# sound.net
KiCad netlist of a schematic drawn in Altium Designer
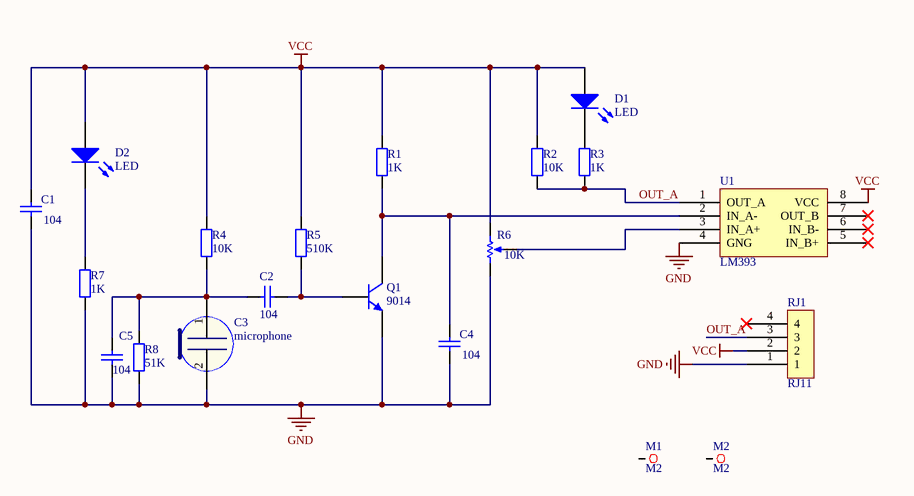
[diagram p0: sound.SchDoc]

(export (version "E")
  (design (tool "Eeschema 10.0.6"))
  (components
    (comp (ref "C1")
      (value "104")
      (footprint "0603_C")
      (description "Capacitor")
      (fields (field (name "Comment") "Cap") (field (name "PUBLISHER") "Altium Limited"))
      (libsource (lib "Miscellaneous Devices") (part "Cap"))
    )
    (comp (ref "C2")
      (value "104")
      (footprint "0603_C")
      (description "Capacitor")
      (fields (field (name "Comment") "Cap") (field (name "PUBLISHER") "Altium Limited"))
      (libsource (lib "Miscellaneous Devices") (part "Cap"))
    )
    (comp (ref "C3")
      (value "microphone")
      (footprint "Microphone")
      (libsource (lib "sound") (part "microphone"))
    )
    (comp (ref "C4")
      (value "104")
      (footprint "0603_C")
      (description "Capacitor")
      (fields (field (name "Comment") "Cap") (field (name "PUBLISHER") "Altium Limited"))
      (libsource (lib "Miscellaneous Devices") (part "Cap"))
    )
    (comp (ref "C5")
      (value "104")
      (footprint "0603_C")
      (description "Capacitor")
      (fields (field (name "Comment") "Cap") (field (name "PUBLISHER") "Altium Limited"))
      (libsource (lib "Miscellaneous Devices") (part "Cap"))
    )
    (comp (ref "D1")
      (value "LED")
      (footprint "0805")
      (description "Typical RED GaAs LED")
      (fields (field (name "PUBLISHER") "Altium Limited"))
      (libsource (lib "Miscellaneous Devices") (part "LED1"))
    )
    (comp (ref "D2")
      (value "LED")
      (footprint "0805")
      (description "Typical RED GaAs LED")
      (fields (field (name "PUBLISHER") "Altium Limited"))
      (libsource (lib "Miscellaneous Devices") (part "LED1"))
    )
    (comp (ref "M1") (value "M2") (footprint "M2") (libsource (lib "QQW-1.SCHLIB") (part "M3")))
    (comp (ref "M2") (value "M2") (footprint "M2") (libsource (lib "QQW-1.SCHLIB") (part "M3")))
    (comp (ref "Q1")
      (value "9014")
      (footprint "SOT23")
      (description "NPN General Purpose Amplifier")
      (fields (field (name "PUBLISHER") "Altium Limited"))
      (libsource (lib "Miscellaneous Devices") (part "2N3904"))
    )
    (comp (ref "R1")
      (value "1K")
      (footprint "0603_R")
      (description "Resistor")
      (fields (field (name "Comment") "Res2") (field (name "PUBLISHER") "Altium Limited"))
      (libsource (lib "Miscellaneous Devices") (part "Res2"))
    )
    (comp (ref "R2")
      (value "10K")
      (footprint "0603_R")
      (description "Resistor")
      (fields (field (name "Comment") "Res2") (field (name "PUBLISHER") "Altium Limited"))
      (libsource (lib "Miscellaneous Devices") (part "Res2"))
    )
    (comp (ref "R3")
      (value "1K")
      (footprint "0603_R")
      (description "Resistor")
      (fields (field (name "Comment") "Res2") (field (name "PUBLISHER") "Altium Limited"))
      (libsource (lib "Miscellaneous Devices") (part "Res2"))
    )
    (comp (ref "R4")
      (value "10K")
      (footprint "0603_R")
      (description "Resistor")
      (fields (field (name "Comment") "Res2") (field (name "PUBLISHER") "Altium Limited"))
      (libsource (lib "Miscellaneous Devices") (part "Res2"))
    )
    (comp (ref "R5")
      (value "510K")
      (footprint "0603_R")
      (description "Resistor")
      (fields (field (name "Comment") "Res2") (field (name "PUBLISHER") "Altium Limited"))
      (libsource (lib "Miscellaneous Devices") (part "Res2"))
    )
    (comp (ref "R6")
      (value "10K")
      (footprint "电位器")
      (description "Potentiometer")
      (fields (field (name "Comment") "RPot") (field (name "PUBLISHER") "Altium Limited"))
      (libsource (lib "Miscellaneous Devices") (part "RPot"))
    )
    (comp (ref "R7")
      (value "1K")
      (footprint "0603_R")
      (description "Resistor")
      (fields (field (name "Comment") "Res2") (field (name "PUBLISHER") "Altium Limited"))
      (libsource (lib "Miscellaneous Devices") (part "Res2"))
    )
    (comp (ref "R8")
      (value "51K")
      (footprint "0603_R")
      (description "Resistor")
      (fields (field (name "Comment") "Res2") (field (name "PUBLISHER") "Altium Limited"))
      (libsource (lib "Miscellaneous Devices") (part "Res2"))
    )
    (comp (ref "RJ1") (value "RJ11") (footprint "RJ11") (libsource (lib "少儿智能车") (part "RJ11")))
    (comp (ref "U1") (value "LM393") (footprint "SO-8") (libsource (lib "Infrared") (part "LM393")))
  )
  (nets
    (net (code "1") (name "/OUT_A") (class "Default")
      (node (ref "R2") (pin "1") (pinfunction "1_1") (pintype "passive"))
      (node (ref "R3") (pin "1") (pinfunction "1_1") (pintype "passive"))
      (node (ref "RJ1") (pin "3") (pinfunction "3_3") (pintype "passive"))
      (node (ref "U1") (pin "1") (pinfunction "OUT_A_1") (pintype "passive"))
    )
    (net (code "2") (name "GND") (class "Default")
      (node (ref "C1") (pin "1") (pinfunction "1_1") (pintype "passive"))
      (node (ref "C3") (pin "2") (pinfunction "2_2") (pintype "passive"))
      (node (ref "C4") (pin "1") (pinfunction "1_1") (pintype "passive"))
      (node (ref "C5") (pin "2") (pinfunction "2_2") (pintype "passive"))
      (node (ref "Q1") (pin "1") (pinfunction "E_1") (pintype "passive"))
      (node (ref "R6") (pin "1") (pinfunction "TOP_1") (pintype "passive"))
      (node (ref "R7") (pin "1") (pinfunction "1_1") (pintype "passive"))
      (node (ref "R8") (pin "1") (pinfunction "1_1") (pintype "passive"))
      (node (ref "RJ1") (pin "1") (pinfunction "1_1") (pintype "passive"))
      (node (ref "U1") (pin "4") (pinfunction "GNG_4") (pintype "passive"))
    )
    (net (code "3") (name "Net-(C2-Pad2)") (class "Default")
      (node (ref "C2") (pin "2") (pinfunction "2_2") (pintype "passive"))
      (node (ref "C3") (pin "1") (pinfunction "1_1") (pintype "passive"))
      (node (ref "C5") (pin "1") (pinfunction "1_1") (pintype "passive"))
      (node (ref "R4") (pin "1") (pinfunction "1_1") (pintype "passive"))
      (node (ref "R8") (pin "2") (pinfunction "2_2") (pintype "passive"))
    )
    (net (code "4") (name "Net-(D1-K)") (class "Default")
      (node (ref "D1") (pin "2") (pinfunction "K_2") (pintype "passive"))
      (node (ref "R3") (pin "2") (pinfunction "2_2") (pintype "passive"))
    )
    (net (code "5") (name "Net-(D2-K)") (class "Default")
      (node (ref "D2") (pin "2") (pinfunction "K_2") (pintype "passive"))
      (node (ref "R7") (pin "2") (pinfunction "2_2") (pintype "passive"))
    )
    (net (code "6") (name "Net-(Q1-B)") (class "Default")
      (node (ref "C2") (pin "1") (pinfunction "1_1") (pintype "passive"))
      (node (ref "Q1") (pin "2") (pinfunction "B_2") (pintype "passive"))
      (node (ref "R5") (pin "1") (pinfunction "1_1") (pintype "passive"))
    )
    (net (code "7") (name "Net-(Q1-C)") (class "Default")
      (node (ref "C4") (pin "2") (pinfunction "2_2") (pintype "passive"))
      (node (ref "Q1") (pin "3") (pinfunction "C_3") (pintype "passive"))
      (node (ref "R1") (pin "1") (pinfunction "1_1") (pintype "passive"))
      (node (ref "U1") (pin "2") (pinfunction "IN_A-_2") (pintype "passive"))
    )
    (net (code "8") (name "Net-(R6-TAP)") (class "Default")
      (node (ref "R6") (pin "3") (pinfunction "TAP_3") (pintype "passive"))
      (node (ref "U1") (pin "3") (pinfunction "IN_A+_3") (pintype "passive"))
    )
    (net (code "9") (name "VCC") (class "Default")
      (node (ref "C1") (pin "2") (pinfunction "2_2") (pintype "passive"))
      (node (ref "D1") (pin "1") (pinfunction "A_1") (pintype "passive"))
      (node (ref "D2") (pin "1") (pinfunction "A_1") (pintype "passive"))
      (node (ref "R1") (pin "2") (pinfunction "2_2") (pintype "passive"))
      (node (ref "R2") (pin "2") (pinfunction "2_2") (pintype "passive"))
      (node (ref "R4") (pin "2") (pinfunction "2_2") (pintype "passive"))
      (node (ref "R5") (pin "2") (pinfunction "2_2") (pintype "passive"))
      (node (ref "R6") (pin "2") (pinfunction "BOT_2") (pintype "passive"))
      (node (ref "RJ1") (pin "2") (pinfunction "2_2") (pintype "passive"))
      (node (ref "U1") (pin "8") (pinfunction "VCC_8") (pintype "passive"))
    )
    (net (code "10") (name "unconnected-(M1-Pad0)") (class "Default")
      (node (ref "M1") (pin "0") (pinfunction "0_0") (pintype "passive"))
    )
    (net (code "11") (name "unconnected-(M2-Pad0)") (class "Default")
      (node (ref "M2") (pin "0") (pinfunction "0_0") (pintype "passive"))
    )
    (net (code "12") (name "unconnected-(RJ1-Pad4)") (class "Default")
      (node (ref "RJ1") (pin "4") (pinfunction "4_4") (pintype "passive+no_connect"))
    )
    (net (code "13") (name "unconnected-(U1-IN_B+-Pad5)") (class "Default")
      (node (ref "U1") (pin "5") (pinfunction "IN_B+_5") (pintype "passive+no_connect"))
    )
    (net (code "14") (name "unconnected-(U1-IN_B--Pad6)") (class "Default")
      (node (ref "U1") (pin "6") (pinfunction "IN_B-_6") (pintype "passive+no_connect"))
    )
    (net (code "15") (name "unconnected-(U1-OUT_B-Pad7)") (class "Default")
      (node (ref "U1") (pin "7") (pinfunction "OUT_B_7") (pintype "passive+no_connect"))
    )
  )
)
